# HONG_NGOAI.net
KiCad netlist of a schematic drawn in Altium Designer
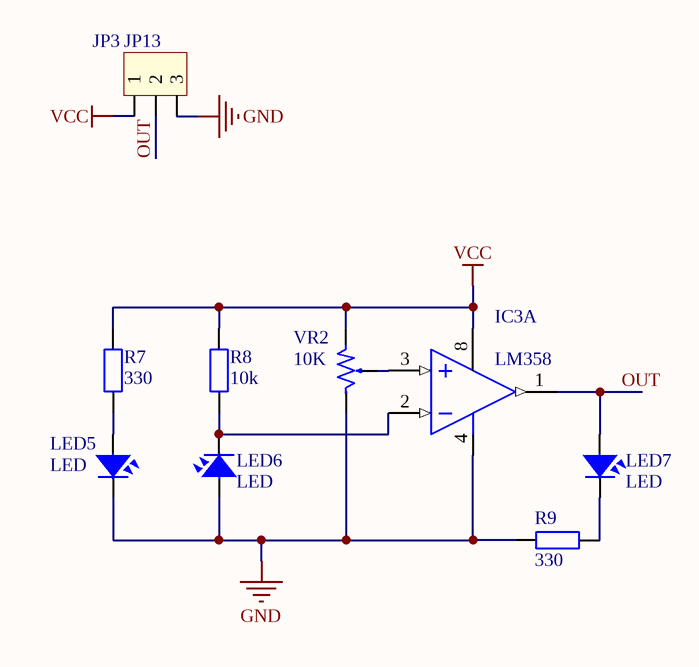
[diagram p0: HONG NGOAI.SchDoc]

(export (version "E")
  (design (tool "Eeschema 10.0.6"))
  (components
    (comp (ref "IC3")
      (value "LM358")
      (footprint "DIP8/W0.3")
      (description "Low-Power Dual Operational Amplifier")
      (libsource (lib "syhaunguyen") (part "LM358"))
    )
    (comp (ref "JP13")
      (value "JP3")
      (footprint "CON3")
      (description "Connector 3")
      (libsource (lib "syhaunguyen") (part "Con3"))
    )
    (comp (ref "LED5")
      (value "LED")
      (footprint "LED-3")
      (description "Led  Vuong")
      (libsource (lib "syhaunguyen") (part "LED"))
    )
    (comp (ref "LED6")
      (value "LED")
      (footprint "LED-3")
      (description "Led  Vuong")
      (libsource (lib "syhaunguyen") (part "LED"))
    )
    (comp (ref "LED7")
      (value "LED")
      (footprint "LED-3")
      (description "Led  Vuong")
      (libsource (lib "syhaunguyen") (part "LED"))
    )
    (comp (ref "R7")
      (value "330")
      (footprint "R1/4W")
      (description "Resistor 1/4W")
      (libsource (lib "syhaunguyen") (part "R1/4W"))
    )
    (comp (ref "R8")
      (value "10k")
      (footprint "R1/4W")
      (description "Resistor 1/4W")
      (libsource (lib "syhaunguyen") (part "R1/4W"))
    )
    (comp (ref "R9")
      (value "330")
      (footprint "R1/4W")
      (description "Resistor 1/4W")
      (libsource (lib "syhaunguyen") (part "R1/4W"))
    )
    (comp (ref "VR2")
      (value "10K")
      (footprint "VR1")
      (description "Var Resistor")
      (libsource (lib "syhaunguyen") (part "VR1"))
    )
  )
  (nets
    (net (code "1") (name "/OUT") (class "Default")
      (node (ref "IC3") (pin "1") (pinfunction "OUT_1") (pintype "output"))
      (node (ref "JP13") (pin "2") (pinfunction "2_2") (pintype "passive"))
      (node (ref "LED7") (pin "1") (pinfunction "1_1") (pintype "passive"))
    )
    (net (code "2") (name "GND") (class "Default")
      (node (ref "IC3") (pin "4") (pinfunction "-V_4") (pintype "passive"))
      (node (ref "JP13") (pin "3") (pinfunction "3_3") (pintype "passive"))
      (node (ref "LED5") (pin "2") (pinfunction "2_2") (pintype "passive"))
      (node (ref "LED6") (pin "1") (pinfunction "1_1") (pintype "passive"))
      (node (ref "R9") (pin "2") (pinfunction "2_2") (pintype "passive"))
      (node (ref "VR2") (pin "3") (pinfunction "3_3") (pintype "passive"))
    )
    (net (code "3") (name "Net-(IC3A-IN+)") (class "Default")
      (node (ref "IC3") (pin "3") (pinfunction "IN+_3") (pintype "input"))
      (node (ref "VR2") (pin "2") (pinfunction "2_2") (pintype "passive"))
    )
    (net (code "4") (name "Net-(IC3A-IN-)") (class "Default")
      (node (ref "IC3") (pin "2") (pinfunction "IN-_2") (pintype "input"))
      (node (ref "LED6") (pin "2") (pinfunction "2_2") (pintype "passive"))
      (node (ref "R8") (pin "1") (pinfunction "1_1") (pintype "passive"))
    )
    (net (code "5") (name "Net-(LED5-Pad1)") (class "Default")
      (node (ref "LED5") (pin "1") (pinfunction "1_1") (pintype "passive"))
      (node (ref "R7") (pin "1") (pinfunction "1_1") (pintype "passive"))
    )
    (net (code "6") (name "Net-(LED7-Pad2)") (class "Default")
      (node (ref "LED7") (pin "2") (pinfunction "2_2") (pintype "passive"))
      (node (ref "R9") (pin "1") (pinfunction "1_1") (pintype "passive"))
    )
    (net (code "7") (name "VCC") (class "Default")
      (node (ref "IC3") (pin "8") (pinfunction "+V_8") (pintype "passive"))
      (node (ref "JP13") (pin "1") (pinfunction "1_1") (pintype "passive"))
      (node (ref "R7") (pin "2") (pinfunction "2_2") (pintype "passive"))
      (node (ref "R8") (pin "2") (pinfunction "2_2") (pintype "passive"))
      (node (ref "VR2") (pin "1") (pinfunction "1_1") (pintype "passive"))
    )
  )
)
